# ME433_HW6_sch.net
KiCad netlist of a schematic drawn in EAGLE
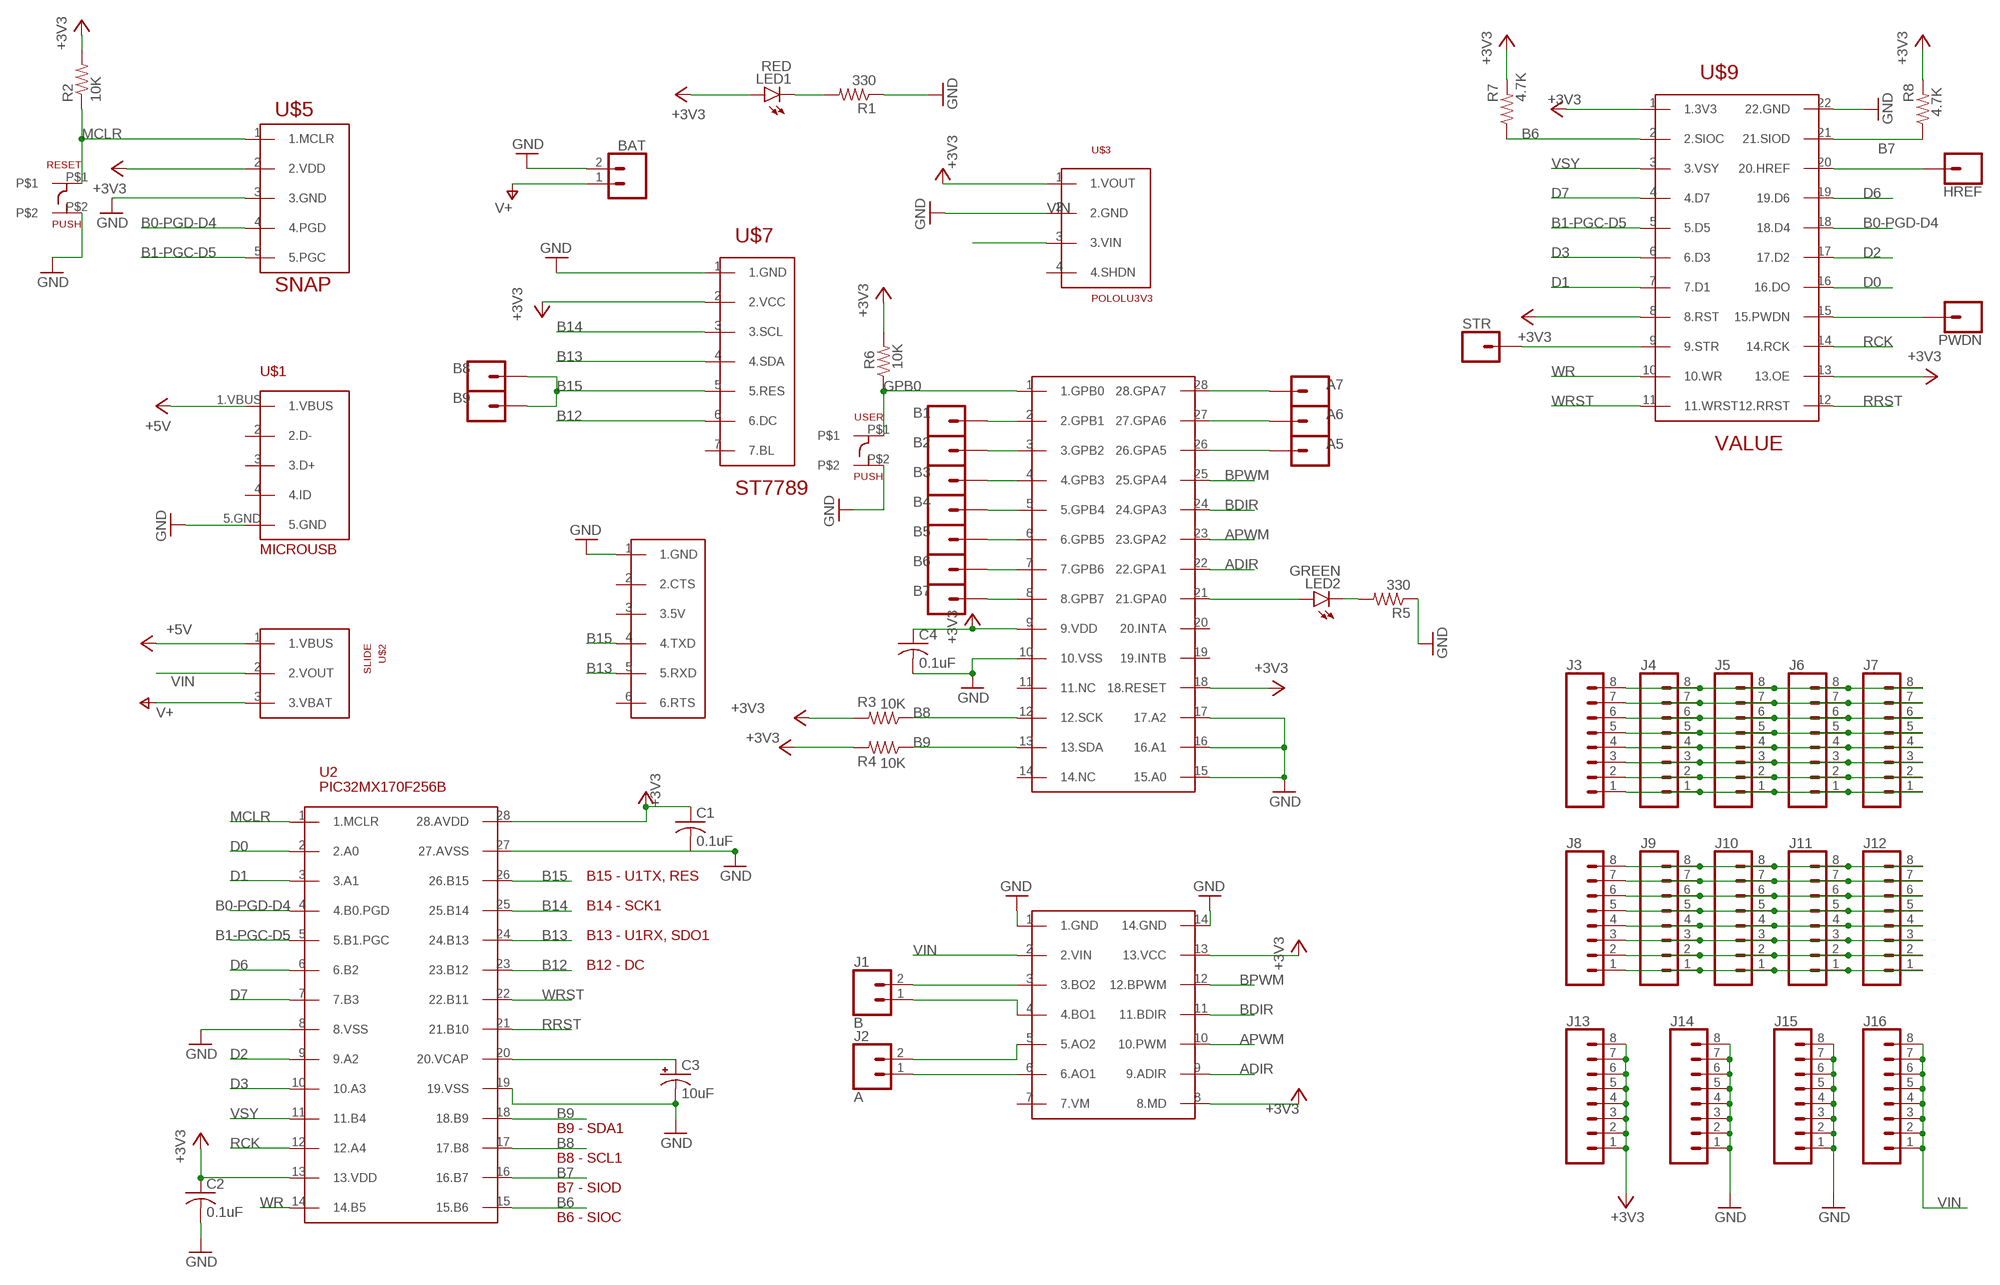
[diagram p0: schematic, sheet 1]

(export (version "E")
  (design (tool "Eeschema 10.0.6"))
  (components
    (comp (ref "A5")
      (value "CONN_01")
      (footprint "eagle-import:1X01")
      (libsource (lib "eagle-import") (part "CONN_01"))
    )
    (comp (ref "A6")
      (value "CONN_01")
      (footprint "eagle-import:1X01")
      (libsource (lib "eagle-import") (part "CONN_01"))
    )
    (comp (ref "A7")
      (value "CONN_01")
      (footprint "eagle-import:1X01")
      (libsource (lib "eagle-import") (part "CONN_01"))
    )
    (comp (ref "B1")
      (value "CONN_01")
      (footprint "eagle-import:1X01")
      (libsource (lib "eagle-import") (part "CONN_01"))
    )
    (comp (ref "B2")
      (value "CONN_01")
      (footprint "eagle-import:1X01")
      (libsource (lib "eagle-import") (part "CONN_01"))
    )
    (comp (ref "B3")
      (value "CONN_01")
      (footprint "eagle-import:1X01")
      (libsource (lib "eagle-import") (part "CONN_01"))
    )
    (comp (ref "B4")
      (value "CONN_01")
      (footprint "eagle-import:1X01")
      (libsource (lib "eagle-import") (part "CONN_01"))
    )
    (comp (ref "B5")
      (value "CONN_01")
      (footprint "eagle-import:1X01")
      (libsource (lib "eagle-import") (part "CONN_01"))
    )
    (comp (ref "B6")
      (value "CONN_01")
      (footprint "eagle-import:1X01")
      (libsource (lib "eagle-import") (part "CONN_01"))
    )
    (comp (ref "B7")
      (value "CONN_01")
      (footprint "eagle-import:1X01")
      (libsource (lib "eagle-import") (part "CONN_01"))
    )
    (comp (ref "B8")
      (value "CONN_01")
      (footprint "eagle-import:1X01")
      (libsource (lib "eagle-import") (part "CONN_01"))
    )
    (comp (ref "B9")
      (value "CONN_01")
      (footprint "eagle-import:1X01")
      (libsource (lib "eagle-import") (part "CONN_01"))
    )
    (comp (ref "BAT")
      (value "CONN_02")
      (footprint "eagle-import:1X02")
      (libsource (lib "eagle-import") (part "CONN_02"))
    )
    (comp (ref "C1")
      (value "0.1uF")
      (footprint "eagle-import:C025-030X050")
      (libsource (lib "eagle-import") (part "C-US025-030X050"))
    )
    (comp (ref "C2")
      (value "0.1uF")
      (footprint "eagle-import:C025-030X050")
      (libsource (lib "eagle-import") (part "C-US025-030X050"))
    )
    (comp (ref "C3")
      (value "10uF")
      (footprint "eagle-import:B45181B")
      (libsource (lib "eagle-import") (part "CPOL-USB45181B"))
    )
    (comp (ref "C4")
      (value "0.1uF")
      (footprint "eagle-import:C025-030X050")
      (libsource (lib "eagle-import") (part "C-US025-030X050"))
    )
    (comp (ref "HREF")
      (value "CONN_01")
      (footprint "eagle-import:1X01")
      (libsource (lib "eagle-import") (part "CONN_01"))
    )
    (comp (ref "J1")
      (value "B")
      (footprint "eagle-import:1X02")
      (libsource (lib "eagle-import") (part "CONN_02"))
    )
    (comp (ref "J2")
      (value "A")
      (footprint "eagle-import:1X02")
      (libsource (lib "eagle-import") (part "CONN_02"))
    )
    (comp (ref "J3")
      (value "CONN_08\"")
      (footprint "eagle-import:1X08")
      (libsource (lib "eagle-import") (part "CONN_08{dblquote}"))
    )
    (comp (ref "J4")
      (value "CONN_08\"")
      (footprint "eagle-import:1X08")
      (libsource (lib "eagle-import") (part "CONN_08{dblquote}"))
    )
    (comp (ref "J5")
      (value "CONN_08\"")
      (footprint "eagle-import:1X08")
      (libsource (lib "eagle-import") (part "CONN_08{dblquote}"))
    )
    (comp (ref "J6")
      (value "CONN_08\"")
      (footprint "eagle-import:1X08")
      (libsource (lib "eagle-import") (part "CONN_08{dblquote}"))
    )
    (comp (ref "J7")
      (value "CONN_08\"")
      (footprint "eagle-import:1X08")
      (libsource (lib "eagle-import") (part "CONN_08{dblquote}"))
    )
    (comp (ref "J8")
      (value "CONN_08\"")
      (footprint "eagle-import:1X08")
      (libsource (lib "eagle-import") (part "CONN_08{dblquote}"))
    )
    (comp (ref "J9")
      (value "CONN_08\"")
      (footprint "eagle-import:1X08")
      (libsource (lib "eagle-import") (part "CONN_08{dblquote}"))
    )
    (comp (ref "J10")
      (value "CONN_08\"")
      (footprint "eagle-import:1X08")
      (libsource (lib "eagle-import") (part "CONN_08{dblquote}"))
    )
    (comp (ref "J11")
      (value "CONN_08\"")
      (footprint "eagle-import:1X08")
      (libsource (lib "eagle-import") (part "CONN_08{dblquote}"))
    )
    (comp (ref "J12")
      (value "CONN_08\"")
      (footprint "eagle-import:1X08")
      (libsource (lib "eagle-import") (part "CONN_08{dblquote}"))
    )
    (comp (ref "J13")
      (value "CONN_08\"")
      (footprint "eagle-import:1X08")
      (libsource (lib "eagle-import") (part "CONN_08{dblquote}"))
    )
    (comp (ref "J14")
      (value "CONN_08\"")
      (footprint "eagle-import:1X08")
      (libsource (lib "eagle-import") (part "CONN_08{dblquote}"))
    )
    (comp (ref "J15")
      (value "CONN_08\"")
      (footprint "eagle-import:1X08")
      (libsource (lib "eagle-import") (part "CONN_08{dblquote}"))
    )
    (comp (ref "J16")
      (value "CONN_08\"")
      (footprint "eagle-import:1X08")
      (libsource (lib "eagle-import") (part "CONN_08{dblquote}"))
    )
    (comp (ref "LED1")
      (value "RED")
      (footprint "eagle-import:LED3MM")
      (libsource (lib "eagle-import") (part "LED3MM"))
    )
    (comp (ref "LED2")
      (value "GREEN")
      (footprint "eagle-import:LED3MM")
      (libsource (lib "eagle-import") (part "LED3MM"))
    )
    (comp (ref "PWDN")
      (value "CONN_01")
      (footprint "eagle-import:1X01")
      (libsource (lib "eagle-import") (part "CONN_01"))
    )
    (comp (ref "R1")
      (value "330")
      (footprint "eagle-import:0207_10")
      (libsource (lib "eagle-import") (part "R-US_0207/10"))
    )
    (comp (ref "R2")
      (value "10K")
      (footprint "eagle-import:0207_10")
      (libsource (lib "eagle-import") (part "R-US_0207/10"))
    )
    (comp (ref "R3")
      (value "10K")
      (footprint "eagle-import:0207_10")
      (libsource (lib "eagle-import") (part "R-US_0207/10"))
    )
    (comp (ref "R4")
      (value "10K")
      (footprint "eagle-import:0207_10")
      (libsource (lib "eagle-import") (part "R-US_0207/10"))
    )
    (comp (ref "R5")
      (value "330")
      (footprint "eagle-import:0207_10")
      (libsource (lib "eagle-import") (part "R-US_0207/10"))
    )
    (comp (ref "R6")
      (value "10K")
      (footprint "eagle-import:0207_10")
      (libsource (lib "eagle-import") (part "R-US_0207/10"))
    )
    (comp (ref "R7")
      (value "4.7K")
      (footprint "eagle-import:0207_10")
      (libsource (lib "eagle-import") (part "R-US_0207/10"))
    )
    (comp (ref "R8")
      (value "4.7K")
      (footprint "eagle-import:0207_10")
      (libsource (lib "eagle-import") (part "R-US_0207/10"))
    )
    (comp (ref "RESET")
      (value "PUSH")
      (footprint "eagle-import:PUSH")
      (libsource (lib "eagle-import") (part "PUSH"))
    )
    (comp (ref "STR")
      (value "CONN_01")
      (footprint "eagle-import:1X01")
      (libsource (lib "eagle-import") (part "CONN_01"))
    )
    (comp (ref "U$1")
      (value "MICROUSB")
      (footprint "eagle-import:MICROUSB")
      (libsource (lib "eagle-import") (part "MICROUSB"))
    )
    (comp (ref "U$2")
      (value "SLIDE")
      (footprint "eagle-import:SLIDE")
      (libsource (lib "eagle-import") (part "SLIDE"))
    )
    (comp (ref "U$3")
      (value "POLOLU3V3")
      (footprint "eagle-import:POLOLU3V3")
      (libsource (lib "eagle-import") (part "POLOLU3V3"))
    )
    (comp (ref "U$4")
      (value "DRV8835")
      (footprint "eagle-import:DRV8835")
      (libsource (lib "eagle-import") (part "DRV8835"))
    )
    (comp (ref "U$5")
      (value "SNAP")
      (footprint "eagle-import:SNAP")
      (libsource (lib "eagle-import") (part "SNAP"))
    )
    (comp (ref "U$6")
      (value "CP2104_FRIEND")
      (footprint "eagle-import:CP2104_FRIEND")
      (libsource (lib "eagle-import") (part "CP2104_FRIEND"))
    )
    (comp (ref "U$7")
      (value "ST7789")
      (footprint "eagle-import:ST7789")
      (libsource (lib "eagle-import") (part "ST7789"))
    )
    (comp (ref "U$8")
      (value "MCP23017")
      (footprint "eagle-import:DIL28-3")
      (libsource (lib "eagle-import") (part "MCP23017"))
    )
    (comp (ref "U$9")
      (value "OV7670FIFO")
      (footprint "eagle-import:OV7670FIFO")
      (libsource (lib "eagle-import") (part "OV7670FIFO"))
    )
    (comp (ref "U2")
      (value "PIC32MX170F256B")
      (footprint "eagle-import:DIL28-3")
      (libsource (lib "eagle-import") (part "PIC32MX170F256B"))
    )
    (comp (ref "USER")
      (value "PUSH")
      (footprint "eagle-import:PUSH")
      (libsource (lib "eagle-import") (part "PUSH"))
    )
  )
  (nets
    (net (code "1") (name "+3V3") (class "Default")
      (node (ref "C1") (pin "1") (pinfunction "1_1") (pintype "passive"))
      (node (ref "C2") (pin "1") (pinfunction "1_1") (pintype "passive"))
      (node (ref "C4") (pin "1") (pinfunction "1_1") (pintype "passive"))
      (node (ref "J13") (pin "1") (pinfunction "1_1") (pintype "passive"))
      (node (ref "J13") (pin "2") (pinfunction "2_2") (pintype "passive"))
      (node (ref "J13") (pin "3") (pinfunction "3_3") (pintype "passive"))
      (node (ref "J13") (pin "4") (pinfunction "4_4") (pintype "passive"))
      (node (ref "J13") (pin "5") (pinfunction "5_5") (pintype "passive"))
      (node (ref "J13") (pin "6") (pinfunction "6_6") (pintype "passive"))
      (node (ref "J13") (pin "7") (pinfunction "7_7") (pintype "passive"))
      (node (ref "J13") (pin "8") (pinfunction "8_8") (pintype "passive"))
      (node (ref "LED1") (pin "A") (pinfunction "A_A") (pintype "passive"))
      (node (ref "R2") (pin "2") (pinfunction "2_2") (pintype "passive"))
      (node (ref "R3") (pin "2") (pinfunction "2_2") (pintype "passive"))
      (node (ref "R4") (pin "2") (pinfunction "2_2") (pintype "passive"))
      (node (ref "R6") (pin "2") (pinfunction "2_2") (pintype "passive"))
      (node (ref "R7") (pin "2") (pinfunction "2_2") (pintype "passive"))
      (node (ref "R8") (pin "2") (pinfunction "2_2") (pintype "passive"))
      (node (ref "U$3") (pin "1") (pinfunction "1.VOUT_1") (pintype "bidirectional"))
      (node (ref "U$4") (pin "13") (pinfunction "13.VCC_13") (pintype "bidirectional"))
      (node (ref "U$4") (pin "8") (pinfunction "8.MD_8") (pintype "bidirectional"))
      (node (ref "U$5") (pin "2") (pinfunction "2.VDD_2") (pintype "bidirectional"))
      (node (ref "U$7") (pin "2") (pinfunction "2.VCC_2") (pintype "bidirectional"))
      (node (ref "U$8") (pin "18") (pinfunction "18.RESET_18") (pintype "bidirectional"))
      (node (ref "U$8") (pin "9") (pinfunction "9.VDD_9") (pintype "bidirectional"))
      (node (ref "U$9") (pin "1") (pinfunction "1.3V3_1") (pintype "bidirectional"))
      (node (ref "U$9") (pin "13") (pinfunction "13.OE_13") (pintype "bidirectional"))
      (node (ref "U$9") (pin "8") (pinfunction "8.RST_8") (pintype "bidirectional"))
      (node (ref "U2") (pin "13") (pinfunction "13.VDD_13") (pintype "bidirectional"))
      (node (ref "U2") (pin "28") (pinfunction "28.AVDD_28") (pintype "bidirectional"))
    )
    (net (code "2") (name "+5V") (class "Default")
      (node (ref "U$1") (pin "1.VBUS") (pinfunction "1.VBUS_1.VBUS") (pintype "bidirectional"))
      (node (ref "U$2") (pin "1") (pinfunction "1.VBUS_1") (pintype "bidirectional"))
    )
    (net (code "3") (name "/ADIR") (class "Default")
      (node (ref "U$4") (pin "9") (pinfunction "9.ADIR_9") (pintype "bidirectional"))
      (node (ref "U$8") (pin "22") (pinfunction "22.GPA1_22") (pintype "bidirectional"))
    )
    (net (code "4") (name "/APWM") (class "Default")
      (node (ref "U$4") (pin "10") (pinfunction "10.PWM_10") (pintype "bidirectional"))
      (node (ref "U$8") (pin "23") (pinfunction "23.GPA2_23") (pintype "bidirectional"))
    )
    (net (code "5") (name "/B0-PGD-D4") (class "Default")
      (node (ref "U$5") (pin "4") (pinfunction "4.PGD_4") (pintype "bidirectional"))
      (node (ref "U$9") (pin "18") (pinfunction "18.D4_18") (pintype "bidirectional"))
      (node (ref "U2") (pin "4") (pinfunction "4.B0.PGD_4") (pintype "bidirectional"))
    )
    (net (code "6") (name "/B1-PGC-D5") (class "Default")
      (node (ref "U$5") (pin "5") (pinfunction "5.PGC_5") (pintype "bidirectional"))
      (node (ref "U$9") (pin "5") (pinfunction "5.D5_5") (pintype "bidirectional"))
      (node (ref "U2") (pin "5") (pinfunction "5.B1.PGC_5") (pintype "bidirectional"))
    )
    (net (code "7") (name "/B6") (class "Default")
      (node (ref "R7") (pin "1") (pinfunction "1_1") (pintype "passive"))
      (node (ref "U$9") (pin "2") (pinfunction "2.SIOC_2") (pintype "bidirectional"))
      (node (ref "U2") (pin "15") (pinfunction "15.B6_15") (pintype "bidirectional"))
    )
    (net (code "8") (name "/B7") (class "Default")
      (node (ref "R8") (pin "1") (pinfunction "1_1") (pintype "passive"))
      (node (ref "U$9") (pin "21") (pinfunction "21.SIOD_21") (pintype "bidirectional"))
      (node (ref "U2") (pin "16") (pinfunction "16.B7_16") (pintype "bidirectional"))
    )
    (net (code "9") (name "/B8") (class "Default")
      (node (ref "R3") (pin "1") (pinfunction "1_1") (pintype "passive"))
      (node (ref "U$8") (pin "12") (pinfunction "12.SCK_12") (pintype "bidirectional"))
      (node (ref "U2") (pin "17") (pinfunction "17.B8_17") (pintype "bidirectional"))
    )
    (net (code "10") (name "/B9") (class "Default")
      (node (ref "R4") (pin "1") (pinfunction "1_1") (pintype "passive"))
      (node (ref "U$8") (pin "13") (pinfunction "13.SDA_13") (pintype "bidirectional"))
      (node (ref "U2") (pin "18") (pinfunction "18.B9_18") (pintype "bidirectional"))
    )
    (net (code "11") (name "/B12") (class "Default")
      (node (ref "U$7") (pin "6") (pinfunction "6.DC_6") (pintype "bidirectional"))
      (node (ref "U2") (pin "23") (pinfunction "23.B12_23") (pintype "bidirectional"))
    )
    (net (code "12") (name "/B13") (class "Default")
      (node (ref "U$6") (pin "5") (pinfunction "5.RXD_5") (pintype "bidirectional"))
      (node (ref "U$7") (pin "4") (pinfunction "4.SDA_4") (pintype "bidirectional"))
      (node (ref "U2") (pin "24") (pinfunction "24.B13_24") (pintype "bidirectional"))
    )
    (net (code "13") (name "/B14") (class "Default")
      (node (ref "U$7") (pin "3") (pinfunction "3.SCL_3") (pintype "bidirectional"))
      (node (ref "U2") (pin "25") (pinfunction "25.B14_25") (pintype "bidirectional"))
    )
    (net (code "14") (name "/B15") (class "Default")
      (node (ref "B8") (pin "1") (pinfunction "1_1") (pintype "passive"))
      (node (ref "B9") (pin "1") (pinfunction "1_1") (pintype "passive"))
      (node (ref "U$6") (pin "4") (pinfunction "4.TXD_4") (pintype "bidirectional"))
      (node (ref "U$7") (pin "5") (pinfunction "5.RES_5") (pintype "bidirectional"))
      (node (ref "U2") (pin "26") (pinfunction "26.B15_26") (pintype "bidirectional"))
    )
    (net (code "15") (name "/BDIR") (class "Default")
      (node (ref "U$4") (pin "11") (pinfunction "11.BDIR_11") (pintype "bidirectional"))
      (node (ref "U$8") (pin "24") (pinfunction "24.GPA3_24") (pintype "bidirectional"))
    )
    (net (code "16") (name "/BPWM") (class "Default")
      (node (ref "U$4") (pin "12") (pinfunction "12.BPWM_12") (pintype "bidirectional"))
      (node (ref "U$8") (pin "25") (pinfunction "25.GPA4_25") (pintype "bidirectional"))
    )
    (net (code "17") (name "/D0") (class "Default")
      (node (ref "U$9") (pin "16") (pinfunction "16.DO_16") (pintype "bidirectional"))
      (node (ref "U2") (pin "2") (pinfunction "2.A0_2") (pintype "bidirectional"))
    )
    (net (code "18") (name "/D1") (class "Default")
      (node (ref "U$9") (pin "7") (pinfunction "7.D1_7") (pintype "bidirectional"))
      (node (ref "U2") (pin "3") (pinfunction "3.A1_3") (pintype "bidirectional"))
    )
    (net (code "19") (name "/D2") (class "Default")
      (node (ref "U$9") (pin "17") (pinfunction "17.D2_17") (pintype "bidirectional"))
      (node (ref "U2") (pin "9") (pinfunction "9.A2_9") (pintype "bidirectional"))
    )
    (net (code "20") (name "/D3") (class "Default")
      (node (ref "U$9") (pin "6") (pinfunction "6.D3_6") (pintype "bidirectional"))
      (node (ref "U2") (pin "10") (pinfunction "10.A3_10") (pintype "bidirectional"))
    )
    (net (code "21") (name "/D6") (class "Default")
      (node (ref "U$9") (pin "19") (pinfunction "19.D6_19") (pintype "bidirectional"))
      (node (ref "U2") (pin "6") (pinfunction "6.B2_6") (pintype "bidirectional"))
    )
    (net (code "22") (name "/D7") (class "Default")
      (node (ref "U$9") (pin "4") (pinfunction "4.D7_4") (pintype "bidirectional"))
      (node (ref "U2") (pin "7") (pinfunction "7.B3_7") (pintype "bidirectional"))
    )
    (net (code "23") (name "/GPB0") (class "Default")
      (node (ref "R6") (pin "1") (pinfunction "1_1") (pintype "passive"))
      (node (ref "U$8") (pin "1") (pinfunction "1.GPB0_1") (pintype "bidirectional"))
      (node (ref "USER") (pin "P$1") (pinfunction "P$1_P$1") (pintype "bidirectional"))
    )
    (net (code "24") (name "/MCLR") (class "Default")
      (node (ref "R2") (pin "1") (pinfunction "1_1") (pintype "passive"))
      (node (ref "RESET") (pin "P$1") (pinfunction "P$1_P$1") (pintype "bidirectional"))
      (node (ref "U$5") (pin "1") (pinfunction "1.MCLR_1") (pintype "bidirectional"))
      (node (ref "U2") (pin "1") (pinfunction "1.MCLR_1") (pintype "bidirectional"))
    )
    (net (code "25") (name "/RCK") (class "Default")
      (node (ref "U$9") (pin "14") (pinfunction "14.RCK_14") (pintype "bidirectional"))
      (node (ref "U2") (pin "12") (pinfunction "12.A4_12") (pintype "bidirectional"))
    )
    (net (code "26") (name "/RRST") (class "Default")
      (node (ref "U$9") (pin "12") (pinfunction "12.RRST_12") (pintype "bidirectional"))
      (node (ref "U2") (pin "21") (pinfunction "21.B10_21") (pintype "bidirectional"))
    )
    (net (code "27") (name "/VIN") (class "Default")
      (node (ref "J16") (pin "1") (pinfunction "1_1") (pintype "passive"))
      (node (ref "J16") (pin "2") (pinfunction "2_2") (pintype "passive"))
      (node (ref "J16") (pin "3") (pinfunction "3_3") (pintype "passive"))
      (node (ref "J16") (pin "4") (pinfunction "4_4") (pintype "passive"))
      (node (ref "J16") (pin "5") (pinfunction "5_5") (pintype "passive"))
      (node (ref "J16") (pin "6") (pinfunction "6_6") (pintype "passive"))
      (node (ref "J16") (pin "7") (pinfunction "7_7") (pintype "passive"))
      (node (ref "J16") (pin "8") (pinfunction "8_8") (pintype "passive"))
      (node (ref "U$2") (pin "2") (pinfunction "2.VOUT_2") (pintype "bidirectional"))
      (node (ref "U$3") (pin "3") (pinfunction "3.VIN_3") (pintype "bidirectional"))
      (node (ref "U$4") (pin "2") (pinfunction "2.VIN_2") (pintype "bidirectional"))
    )
    (net (code "28") (name "/VSY") (class "Default")
      (node (ref "U$9") (pin "3") (pinfunction "3.VSY_3") (pintype "bidirectional"))
      (node (ref "U2") (pin "11") (pinfunction "11.B4_11") (pintype "bidirectional"))
    )
    (net (code "29") (name "/WR") (class "Default")
      (node (ref "U$9") (pin "10") (pinfunction "10.WR_10") (pintype "bidirectional"))
      (node (ref "U2") (pin "14") (pinfunction "14.B5_14") (pintype "bidirectional"))
    )
    (net (code "30") (name "/WRST") (class "Default")
      (node (ref "U$9") (pin "11") (pinfunction "11.WRST_11") (pintype "bidirectional"))
      (node (ref "U2") (pin "22") (pinfunction "22.B11_22") (pintype "bidirectional"))
    )
    (net (code "31") (name "GND") (class "Default")
      (node (ref "BAT") (pin "2") (pinfunction "2_2") (pintype "passive"))
      (node (ref "C1") (pin "2") (pinfunction "2_2") (pintype "passive"))
      (node (ref "C2") (pin "2") (pinfunction "2_2") (pintype "passive"))
      (node (ref "C3") (pin "-") (pinfunction "-_-") (pintype "passive"))
      (node (ref "C4") (pin "2") (pinfunction "2_2") (pintype "passive"))
      (node (ref "J14") (pin "1") (pinfunction "1_1") (pintype "passive"))
      (node (ref "J14") (pin "2") (pinfunction "2_2") (pintype "passive"))
      (node (ref "J14") (pin "3") (pinfunction "3_3") (pintype "passive"))
      (node (ref "J14") (pin "4") (pinfunction "4_4") (pintype "passive"))
      (node (ref "J14") (pin "5") (pinfunction "5_5") (pintype "passive"))
      (node (ref "J14") (pin "6") (pinfunction "6_6") (pintype "passive"))
      (node (ref "J14") (pin "7") (pinfunction "7_7") (pintype "passive"))
      (node (ref "J14") (pin "8") (pinfunction "8_8") (pintype "passive"))
      (node (ref "J15") (pin "1") (pinfunction "1_1") (pintype "passive"))
      (node (ref "J15") (pin "2") (pinfunction "2_2") (pintype "passive"))
      (node (ref "J15") (pin "3") (pinfunction "3_3") (pintype "passive"))
      (node (ref "J15") (pin "4") (pinfunction "4_4") (pintype "passive"))
      (node (ref "J15") (pin "5") (pinfunction "5_5") (pintype "passive"))
      (node (ref "J15") (pin "6") (pinfunction "6_6") (pintype "passive"))
      (node (ref "J15") (pin "7") (pinfunction "7_7") (pintype "passive"))
      (node (ref "J15") (pin "8") (pinfunction "8_8") (pintype "passive"))
      (node (ref "R1") (pin "1") (pinfunction "1_1") (pintype "passive"))
      (node (ref "R5") (pin "1") (pinfunction "1_1") (pintype "passive"))
      (node (ref "RESET") (pin "P$2") (pinfunction "P$2_P$2") (pintype "bidirectional"))
      (node (ref "U$1") (pin "5.GND") (pinfunction "5.GND_5.GND") (pintype "bidirectional"))
      (node (ref "U$3") (pin "2") (pinfunction "2.GND_2") (pintype "bidirectional"))
      (node (ref "U$4") (pin "1") (pinfunction "1.GND_1") (pintype "bidirectional"))
      (node (ref "U$4") (pin "14") (pinfunction "14.GND_14") (pintype "bidirectional"))
      (node (ref "U$5") (pin "3") (pinfunction "3.GND_3") (pintype "bidirectional"))
      (node (ref "U$6") (pin "1") (pinfunction "1.GND_1") (pintype "bidirectional"))
      (node (ref "U$7") (pin "1") (pinfunction "1.GND_1") (pintype "bidirectional"))
      (node (ref "U$8") (pin "10") (pinfunction "10.VSS_10") (pintype "bidirectional"))
      (node (ref "U$8") (pin "15") (pinfunction "15.A0_15") (pintype "bidirectional"))
      (node (ref "U$8") (pin "16") (pinfunction "16.A1_16") (pintype "bidirectional"))
      (node (ref "U$8") (pin "17") (pinfunction "17.A2_17") (pintype "bidirectional"))
      (node (ref "U$9") (pin "22") (pinfunction "22.GND_22") (pintype "bidirectional"))
      (node (ref "U2") (pin "19") (pinfunction "19.VSS_19") (pintype "bidirectional"))
      (node (ref "U2") (pin "27") (pinfunction "27.AVSS_27") (pintype "bidirectional"))
      (node (ref "U2") (pin "8") (pinfunction "8.VSS_8") (pintype "bidirectional"))
      (node (ref "USER") (pin "P$2") (pinfunction "P$2_P$2") (pintype "bidirectional"))
    )
    (net (code "32") (name "Net-(J3-Pad1)") (class "Default")
      (node (ref "J3") (pin "1") (pinfunction "1_1") (pintype "passive"))
      (node (ref "J4") (pin "1") (pinfunction "1_1") (pintype "passive"))
      (node (ref "J5") (pin "1") (pinfunction "1_1") (pintype "passive"))
      (node (ref "J6") (pin "1") (pinfunction "1_1") (pintype "passive"))
      (node (ref "J7") (pin "1") (pinfunction "1_1") (pintype "passive"))
    )
    (net (code "33") (name "Net-(J3-Pad2)") (class "Default")
      (node (ref "J3") (pin "2") (pinfunction "2_2") (pintype "passive"))
      (node (ref "J4") (pin "2") (pinfunction "2_2") (pintype "passive"))
      (node (ref "J5") (pin "2") (pinfunction "2_2") (pintype "passive"))
      (node (ref "J6") (pin "2") (pinfunction "2_2") (pintype "passive"))
      (node (ref "J7") (pin "2") (pinfunction "2_2") (pintype "passive"))
    )
    (net (code "34") (name "Net-(J3-Pad3)") (class "Default")
      (node (ref "J3") (pin "3") (pinfunction "3_3") (pintype "passive"))
      (node (ref "J4") (pin "3") (pinfunction "3_3") (pintype "passive"))
      (node (ref "J5") (pin "3") (pinfunction "3_3") (pintype "passive"))
      (node (ref "J6") (pin "3") (pinfunction "3_3") (pintype "passive"))
      (node (ref "J7") (pin "3") (pinfunction "3_3") (pintype "passive"))
    )
    (net (code "35") (name "Net-(J3-Pad4)") (class "Default")
      (node (ref "J3") (pin "4") (pinfunction "4_4") (pintype "passive"))
      (node (ref "J4") (pin "4") (pinfunction "4_4") (pintype "passive"))
      (node (ref "J5") (pin "4") (pinfunction "4_4") (pintype "passive"))
      (node (ref "J6") (pin "4") (pinfunction "4_4") (pintype "passive"))
      (node (ref "J7") (pin "4") (pinfunction "4_4") (pintype "passive"))
    )
    (net (code "36") (name "Net-(J3-Pad5)") (class "Default")
      (node (ref "J3") (pin "5") (pinfunction "5_5") (pintype "passive"))
      (node (ref "J4") (pin "5") (pinfunction "5_5") (pintype "passive"))
      (node (ref "J5") (pin "5") (pinfunction "5_5") (pintype "passive"))
      (node (ref "J6") (pin "5") (pinfunction "5_5") (pintype "passive"))
      (node (ref "J7") (pin "5") (pinfunction "5_5") (pintype "passive"))
    )
    (net (code "37") (name "Net-(J3-Pad6)") (class "Default")
      (node (ref "J3") (pin "6") (pinfunction "6_6") (pintype "passive"))
      (node (ref "J4") (pin "6") (pinfunction "6_6") (pintype "passive"))
      (node (ref "J5") (pin "6") (pinfunction "6_6") (pintype "passive"))
      (node (ref "J6") (pin "6") (pinfunction "6_6") (pintype "passive"))
      (node (ref "J7") (pin "6") (pinfunction "6_6") (pintype "passive"))
    )
    (net (code "38") (name "Net-(J3-Pad7)") (class "Default")
      (node (ref "J3") (pin "7") (pinfunction "7_7") (pintype "passive"))
      (node (ref "J4") (pin "7") (pinfunction "7_7") (pintype "passive"))
      (node (ref "J5") (pin "7") (pinfunction "7_7") (pintype "passive"))
      (node (ref "J6") (pin "7") (pinfunction "7_7") (pintype "passive"))
      (node (ref "J7") (pin "7") (pinfunction "7_7") (pintype "passive"))
    )
    (net (code "39") (name "Net-(J3-Pad8)") (class "Default")
      (node (ref "J3") (pin "8") (pinfunction "8_8") (pintype "passive"))
      (node (ref "J4") (pin "8") (pinfunction "8_8") (pintype "passive"))
      (node (ref "J5") (pin "8") (pinfunction "8_8") (pintype "passive"))
      (node (ref "J6") (pin "8") (pinfunction "8_8") (pintype "passive"))
      (node (ref "J7") (pin "8") (pinfunction "8_8") (pintype "passive"))
    )
    (net (code "40") (name "Net-(J10-Pad1)") (class "Default")
      (node (ref "J10") (pin "1") (pinfunction "1_1") (pintype "passive"))
      (node (ref "J11") (pin "1") (pinfunction "1_1") (pintype "passive"))
      (node (ref "J12") (pin "1") (pinfunction "1_1") (pintype "passive"))
      (node (ref "J8") (pin "1") (pinfunction "1_1") (pintype "passive"))
      (node (ref "J9") (pin "1") (pinfunction "1_1") (pintype "passive"))
    )
    (net (code "41") (name "Net-(J10-Pad2)") (class "Default")
      (node (ref "J10") (pin "2") (pinfunction "2_2") (pintype "passive"))
      (node (ref "J11") (pin "2") (pinfunction "2_2") (pintype "passive"))
      (node (ref "J12") (pin "2") (pinfunction "2_2") (pintype "passive"))
      (node (ref "J8") (pin "2") (pinfunction "2_2") (pintype "passive"))
      (node (ref "J9") (pin "2") (pinfunction "2_2") (pintype "passive"))
    )
    (net (code "42") (name "Net-(J10-Pad3)") (class "Default")
      (node (ref "J10") (pin "3") (pinfunction "3_3") (pintype "passive"))
      (node (ref "J11") (pin "3") (pinfunction "3_3") (pintype "passive"))
      (node (ref "J12") (pin "3") (pinfunction "3_3") (pintype "passive"))
      (node (ref "J8") (pin "3") (pinfunction "3_3") (pintype "passive"))
      (node (ref "J9") (pin "3") (pinfunction "3_3") (pintype "passive"))
    )
    (net (code "43") (name "Net-(J10-Pad4)") (class "Default")
      (node (ref "J10") (pin "4") (pinfunction "4_4") (pintype "passive"))
      (node (ref "J11") (pin "4") (pinfunction "4_4") (pintype "passive"))
      (node (ref "J12") (pin "4") (pinfunction "4_4") (pintype "passive"))
      (node (ref "J8") (pin "4") (pinfunction "4_4") (pintype "passive"))
      (node (ref "J9") (pin "4") (pinfunction "4_4") (pintype "passive"))
    )
    (net (code "44") (name "Net-(J10-Pad5)") (class "Default")
      (node (ref "J10") (pin "5") (pinfunction "5_5") (pintype "passive"))
      (node (ref "J11") (pin "5") (pinfunction "5_5") (pintype "passive"))
      (node (ref "J12") (pin "5") (pinfunction "5_5") (pintype "passive"))
      (node (ref "J8") (pin "5") (pinfunction "5_5") (pintype "passive"))
      (node (ref "J9") (pin "5") (pinfunction "5_5") (pintype "passive"))
    )
    (net (code "45") (name "Net-(J10-Pad6)") (class "Default")
      (node (ref "J10") (pin "6") (pinfunction "6_6") (pintype "passive"))
      (node (ref "J11") (pin "6") (pinfunction "6_6") (pintype "passive"))
      (node (ref "J12") (pin "6") (pinfunction "6_6") (pintype "passive"))
      (node (ref "J8") (pin "6") (pinfunction "6_6") (pintype "passive"))
      (node (ref "J9") (pin "6") (pinfunction "6_6") (pintype "passive"))
    )
    (net (code "46") (name "Net-(J10-Pad7)") (class "Default")
      (node (ref "J10") (pin "7") (pinfunction "7_7") (pintype "passive"))
      (node (ref "J11") (pin "7") (pinfunction "7_7") (pintype "passive"))
      (node (ref "J12") (pin "7") (pinfunction "7_7") (pintype "passive"))
      (node (ref "J8") (pin "7") (pinfunction "7_7") (pintype "passive"))
      (node (ref "J9") (pin "7") (pinfunction "7_7") (pintype "passive"))
    )
    (net (code "47") (name "Net-(J10-Pad8)") (class "Default")
      (node (ref "J10") (pin "8") (pinfunction "8_8") (pintype "passive"))
      (node (ref "J11") (pin "8") (pinfunction "8_8") (pintype "passive"))
      (node (ref "J12") (pin "8") (pinfunction "8_8") (pintype "passive"))
      (node (ref "J8") (pin "8") (pinfunction "8_8") (pintype "passive"))
      (node (ref "J9") (pin "8") (pinfunction "8_8") (pintype "passive"))
    )
    (net (code "48") (name "Net-(LED1-C)") (class "Default")
      (node (ref "LED1") (pin "K") (pinfunction "C_K") (pintype "passive"))
      (node (ref "R1") (pin "2") (pinfunction "2_2") (pintype "passive"))
    )
    (net (code "49") (name "Net-(LED2-C)") (class "Default")
      (node (ref "LED2") (pin "K") (pinfunction "C_K") (pintype "passive"))
      (node (ref "R5") (pin "2") (pinfunction "2_2") (pintype "passive"))
    )
    (net (code "50") (name "Net-(U$4-3.BO2)") (class "Default")
      (node (ref "J1") (pin "2") (pinfunction "2_2") (pintype "passive"))
      (node (ref "U$4") (pin "3") (pinfunction "3.BO2_3") (pintype "bidirectional"))
    )
    (net (code "51") (name "Net-(U$4-4.BO1)") (class "Default")
      (node (ref "J1") (pin "1") (pinfunction "1_1") (pintype "passive"))
      (node (ref "U$4") (pin "4") (pinfunction "4.BO1_4") (pintype "bidirectional"))
    )
    (net (code "52") (name "Net-(U$4-5.AO2)") (class "Default")
      (node (ref "J2") (pin "2") (pinfunction "2_2") (pintype "passive"))
      (node (ref "U$4") (pin "5") (pinfunction "5.AO2_5") (pintype "bidirectional"))
    )
    (net (code "53") (name "Net-(U$4-6.AO1)") (class "Default")
      (node (ref "J2") (pin "1") (pinfunction "1_1") (pintype "passive"))
      (node (ref "U$4") (pin "6") (pinfunction "6.AO1_6") (pintype "bidirectional"))
    )
    (net (code "54") (name "Net-(U$8-2.GPB1)") (class "Default")
      (node (ref "B1") (pin "1") (pinfunction "1_1") (pintype "passive"))
      (node (ref "U$8") (pin "2") (pinfunction "2.GPB1_2") (pintype "bidirectional"))
    )
    (net (code "55") (name "Net-(U$8-3.GPB2)") (class "Default")
      (node (ref "B2") (pin "1") (pinfunction "1_1") (pintype "passive"))
      (node (ref "U$8") (pin "3") (pinfunction "3.GPB2_3") (pintype "bidirectional"))
    )
    (net (code "56") (name "Net-(U$8-4.GPB3)") (class "Default")
      (node (ref "B3") (pin "1") (pinfunction "1_1") (pintype "passive"))
      (node (ref "U$8") (pin "4") (pinfunction "4.GPB3_4") (pintype "bidirectional"))
    )
    (net (code "57") (name "Net-(U$8-5.GPB4)") (class "Default")
      (node (ref "B4") (pin "1") (pinfunction "1_1") (pintype "passive"))
      (node (ref "U$8") (pin "5") (pinfunction "5.GPB4_5") (pintype "bidirectional"))
    )
    (net (code "58") (name "Net-(U$8-6.GPB5)") (class "Default")
      (node (ref "B5") (pin "1") (pinfunction "1_1") (pintype "passive"))
      (node (ref "U$8") (pin "6") (pinfunction "6.GPB5_6") (pintype "bidirectional"))
    )
    (net (code "59") (name "Net-(U$8-7.GPB6)") (class "Default")
      (node (ref "B6") (pin "1") (pinfunction "1_1") (pintype "passive"))
      (node (ref "U$8") (pin "7") (pinfunction "7.GPB6_7") (pintype "bidirectional"))
    )
    (net (code "60") (name "Net-(U$8-8.GPB7)") (class "Default")
      (node (ref "B7") (pin "1") (pinfunction "1_1") (pintype "passive"))
      (node (ref "U$8") (pin "8") (pinfunction "8.GPB7_8") (pintype "bidirectional"))
    )
    (net (code "61") (name "Net-(U$8-21.GPA0)") (class "Default")
      (node (ref "LED2") (pin "A") (pinfunction "A_A") (pintype "passive"))
      (node (ref "U$8") (pin "21") (pinfunction "21.GPA0_21") (pintype "bidirectional"))
    )
    (net (code "62") (name "Net-(U$8-26.GPA5)") (class "Default")
      (node (ref "A5") (pin "1") (pinfunction "1_1") (pintype "passive"))
      (node (ref "U$8") (pin "26") (pinfunction "26.GPA5_26") (pintype "bidirectional"))
    )
    (net (code "63") (name "Net-(U$8-27.GPA6)") (class "Default")
      (node (ref "A6") (pin "1") (pinfunction "1_1") (pintype "passive"))
      (node (ref "U$8") (pin "27") (pinfunction "27.GPA6_27") (pintype "bidirectional"))
    )
    (net (code "64") (name "Net-(U$8-28.GPA7)") (class "Default")
      (node (ref "A7") (pin "1") (pinfunction "1_1") (pintype "passive"))
      (node (ref "U$8") (pin "28") (pinfunction "28.GPA7_28") (pintype "bidirectional"))
    )
    (net (code "65") (name "Net-(U$9-9.STR)") (class "Default")
      (node (ref "STR") (pin "1") (pinfunction "1_1") (pintype "passive"))
      (node (ref "U$9") (pin "9") (pinfunction "9.STR_9") (pintype "bidirectional"))
    )
    (net (code "66") (name "Net-(U$9-15.PWDN)") (class "Default")
      (node (ref "PWDN") (pin "1") (pinfunction "1_1") (pintype "passive"))
      (node (ref "U$9") (pin "15") (pinfunction "15.PWDN_15") (pintype "bidirectional"))
    )
    (net (code "67") (name "Net-(U$9-20.HREF)") (class "Default")
      (node (ref "HREF") (pin "1") (pinfunction "1_1") (pintype "passive"))
      (node (ref "U$9") (pin "20") (pinfunction "20.HREF_20") (pintype "bidirectional"))
    )
    (net (code "68") (name "Net-(U2-20.VCAP)") (class "Default")
      (node (ref "C3") (pin "+") (pinfunction "+_+") (pintype "passive"))
      (node (ref "U2") (pin "20") (pinfunction "20.VCAP_20") (pintype "bidirectional"))
    )
    (net (code "69") (name "V+") (class "Default")
      (node (ref "BAT") (pin "1") (pinfunction "1_1") (pintype "passive"))
      (node (ref "U$2") (pin "3") (pinfunction "3.VBAT_3") (pintype "bidirectional"))
    )
    (net (code "70") (name "unconnected-(U$1-2.D--Pad2)") (class "Default")
      (node (ref "U$1") (pin "2") (pinfunction "2.D-_2") (pintype "bidirectional"))
    )
    (net (code "71") (name "unconnected-(U$1-3.D+-Pad3)") (class "Default")
      (node (ref "U$1") (pin "3") (pinfunction "3.D+_3") (pintype "bidirectional"))
    )
    (net (code "72") (name "unconnected-(U$1-4.ID-Pad4)") (class "Default")
      (node (ref "U$1") (pin "4") (pinfunction "4.ID_4") (pintype "bidirectional"))
    )
    (net (code "73") (name "unconnected-(U$3-4.SHDN-Pad4)") (class "Default")
      (node (ref "U$3") (pin "4") (pinfunction "4.SHDN_4") (pintype "bidirectional"))
    )
    (net (code "74") (name "unconnected-(U$4-7.VM-Pad7)") (class "Default")
      (node (ref "U$4") (pin "7") (pinfunction "7.VM_7") (pintype "bidirectional"))
    )
    (net (code "75") (name "unconnected-(U$6-2.CTS-Pad2)") (class "Default")
      (node (ref "U$6") (pin "2") (pinfunction "2.CTS_2") (pintype "bidirectional"))
    )
    (net (code "76") (name "unconnected-(U$6-3.5V-Pad3)") (class "Default")
      (node (ref "U$6") (pin "3") (pinfunction "3.5V_3") (pintype "bidirectional"))
    )
    (net (code "77") (name "unconnected-(U$6-6.RTS-Pad6)") (class "Default")
      (node (ref "U$6") (pin "6") (pinfunction "6.RTS_6") (pintype "bidirectional"))
    )
    (net (code "78") (name "unconnected-(U$7-7.BL-Pad7)") (class "Default")
      (node (ref "U$7") (pin "7") (pinfunction "7.BL_7") (pintype "bidirectional"))
    )
    (net (code "79") (name "unconnected-(U$8-11.NC-Pad11)") (class "Default")
      (node (ref "U$8") (pin "11") (pinfunction "11.NC_11") (pintype "bidirectional"))
    )
    (net (code "80") (name "unconnected-(U$8-14.NC-Pad14)") (class "Default")
      (node (ref "U$8") (pin "14") (pinfunction "14.NC_14") (pintype "bidirectional"))
    )
    (net (code "81") (name "unconnected-(U$8-19.INTB-Pad19)") (class "Default")
      (node (ref "U$8") (pin "19") (pinfunction "19.INTB_19") (pintype "bidirectional"))
    )
    (net (code "82") (name "unconnected-(U$8-20.INTA-Pad20)") (class "Default")
      (node (ref "U$8") (pin "20") (pinfunction "20.INTA_20") (pintype "bidirectional"))
    )
  )
)
